# USB_3_0_eMMC.net
KiCad netlist of a schematic drawn in EAGLE
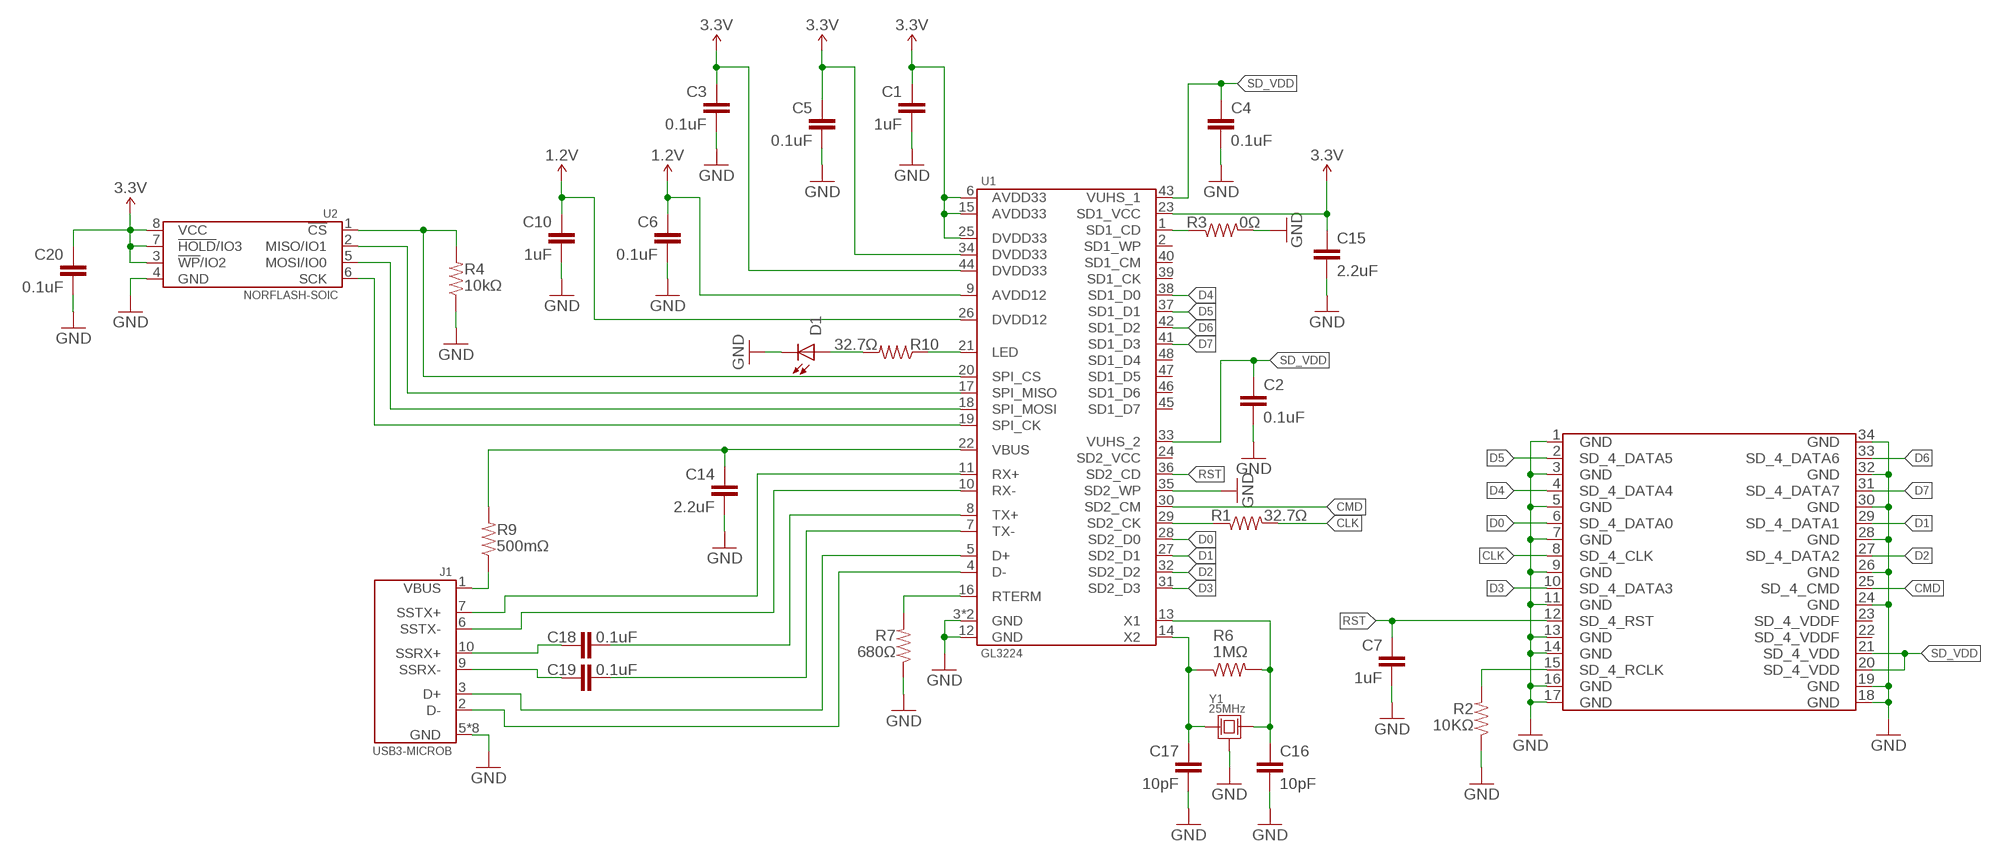
[diagram p0: schematic, sheet 1]

(export (version "E")
  (design (tool "Eeschema 10.0.6"))
  (components
    (comp (ref "C1")
      (value "1uF")
      (footprint "eagle-import:0402-CAP")
      (libsource (lib "eagle-import") (part "CAP-0402"))
    )
    (comp (ref "C2")
      (value "0.1uF")
      (footprint "eagle-import:0402-CAP")
      (libsource (lib "eagle-import") (part "CAP-0402"))
    )
    (comp (ref "C3")
      (value "0.1uF")
      (footprint "eagle-import:0402-CAP")
      (libsource (lib "eagle-import") (part "CAP-0402"))
    )
    (comp (ref "C4")
      (value "0.1uF")
      (footprint "eagle-import:0402-CAP")
      (libsource (lib "eagle-import") (part "CAP-0402"))
    )
    (comp (ref "C5")
      (value "0.1uF")
      (footprint "eagle-import:0402-CAP")
      (libsource (lib "eagle-import") (part "CAP-0402"))
    )
    (comp (ref "C6")
      (value "0.1uF")
      (footprint "eagle-import:0402-CAP")
      (libsource (lib "eagle-import") (part "CAP-0402"))
    )
    (comp (ref "C7")
      (value "1uF")
      (footprint "eagle-import:0402-CAP")
      (libsource (lib "eagle-import") (part "CAP-0402"))
    )
    (comp (ref "C10")
      (value "1uF")
      (footprint "eagle-import:0402-CAP")
      (libsource (lib "eagle-import") (part "CAP-0402"))
    )
    (comp (ref "C14")
      (value "2.2uF")
      (footprint "eagle-import:0402-CAP")
      (libsource (lib "eagle-import") (part "CAP-0402"))
    )
    (comp (ref "C15")
      (value "2.2uF")
      (footprint "eagle-import:0402-CAP")
      (libsource (lib "eagle-import") (part "CAP-0402"))
    )
    (comp (ref "C16")
      (value "10pF")
      (footprint "eagle-import:0402-CAP")
      (libsource (lib "eagle-import") (part "CAP-0402"))
    )
    (comp (ref "C17")
      (value "10pF")
      (footprint "eagle-import:0402-CAP")
      (libsource (lib "eagle-import") (part "CAP-0402"))
    )
    (comp (ref "C18")
      (value "0.1uF")
      (footprint "eagle-import:0402-CAP")
      (libsource (lib "eagle-import") (part "CAP-0402"))
    )
    (comp (ref "C19")
      (value "0.1uF")
      (footprint "eagle-import:0402-CAP")
      (libsource (lib "eagle-import") (part "CAP-0402"))
    )
    (comp (ref "C20")
      (value "0.1uF")
      (footprint "eagle-import:0402-CAP")
      (libsource (lib "eagle-import") (part "CAP-0402"))
    )
    (comp (ref "D1")
      (value "LED-0603")
      (footprint "eagle-import:0603-LED")
      (libsource (lib "eagle-import") (part "LED-0603"))
    )
    (comp (ref "J1")
      (value "USB3-MICROB")
      (footprint "eagle-import:USB-MICROB-3.1")
      (libsource (lib "eagle-import") (part "USB3-MICROB"))
    )
    (comp (ref "R1")
      (value "32.7Ω")
      (footprint "eagle-import:0402-RES")
      (libsource (lib "eagle-import") (part "RESISTOR-0402"))
    )
    (comp (ref "R2")
      (value "10KΩ")
      (footprint "eagle-import:0402-RES")
      (libsource (lib "eagle-import") (part "RESISTOR-0402"))
    )
    (comp (ref "R3")
      (value "0Ω")
      (footprint "eagle-import:0402-RES")
      (libsource (lib "eagle-import") (part "RESISTOR-0402"))
    )
    (comp (ref "R4")
      (value "10kΩ")
      (footprint "eagle-import:0402-RES")
      (libsource (lib "eagle-import") (part "RESISTOR-0402"))
    )
    (comp (ref "R6")
      (value "1MΩ")
      (footprint "eagle-import:0402-RES")
      (libsource (lib "eagle-import") (part "RESISTOR-0402"))
    )
    (comp (ref "R7")
      (value "680Ω")
      (footprint "eagle-import:0402-RES")
      (libsource (lib "eagle-import") (part "RESISTOR-0402"))
    )
    (comp (ref "R9")
      (value "500mΩ")
      (footprint "eagle-import:0805-RES")
      (libsource (lib "eagle-import") (part "RESISTOR-0805"))
    )
    (comp (ref "R10")
      (value "32.7Ω")
      (footprint "eagle-import:0402-RES")
      (libsource (lib "eagle-import") (part "RESISTOR-0402"))
    )
    (comp (ref "U1")
      (value "GL3224")
      (footprint "eagle-import:QFN48")
      (libsource (lib "eagle-import") (part "GL3224"))
    )
    (comp (ref "U2")
      (value "NORFLASH-SOIC")
      (footprint "eagle-import:SOIC-8")
      (libsource (lib "eagle-import") (part "NORFLASH-SOIC"))
    )
    (comp (ref "Y1")
      (value "25MHz")
      (footprint "eagle-import:FA-238")
      (libsource (lib "eagle-import") (part "CRYSTAL-3.2X2.5"))
    )
  )
  (nets
    (net (code "1") (name "1.2V") (class "Default")
      (node (ref "C10") (pin "1") (pinfunction "1_1") (pintype "passive"))
      (node (ref "C6") (pin "1") (pinfunction "1_1") (pintype "passive"))
      (node (ref "U1") (pin "26") (pinfunction "DVDD12_26") (pintype "bidirectional"))
      (node (ref "U1") (pin "9") (pinfunction "AVDD12_9") (pintype "bidirectional"))
    )
    (net (code "2") (name "3.3V") (class "Default")
      (node (ref "C1") (pin "1") (pinfunction "1_1") (pintype "passive"))
      (node (ref "C15") (pin "1") (pinfunction "1_1") (pintype "passive"))
      (node (ref "C20") (pin "1") (pinfunction "1_1") (pintype "passive"))
      (node (ref "C3") (pin "1") (pinfunction "1_1") (pintype "passive"))
      (node (ref "C5") (pin "1") (pinfunction "1_1") (pintype "passive"))
      (node (ref "U1") (pin "15") (pinfunction "AVDD33_15") (pintype "bidirectional"))
      (node (ref "U1") (pin "23") (pinfunction "SD1_VCC_23") (pintype "bidirectional"))
      (node (ref "U1") (pin "25") (pinfunction "DVDD33_25") (pintype "bidirectional"))
      (node (ref "U1") (pin "34") (pinfunction "DVDD33_34") (pintype "bidirectional"))
      (node (ref "U1") (pin "44") (pinfunction "DVDD33_44") (pintype "bidirectional"))
      (node (ref "U1") (pin "6") (pinfunction "AVDD33_6") (pintype "bidirectional"))
      (node (ref "U2") (pin "3") (pinfunction "~{WP}/IO2_3") (pintype "bidirectional"))
      (node (ref "U2") (pin "7") (pinfunction "~{HOLD}/IO3_7") (pintype "bidirectional"))
      (node (ref "U2") (pin "8") (pinfunction "VCC_8") (pintype "bidirectional"))
    )
    (net (code "3") (name "CLK") (class "Default")
      (node (ref "R1") (pin "2") (pinfunction "2_2") (pintype "passive"))
    )
    (net (code "4") (name "CMD") (class "Default")
      (node (ref "U1") (pin "30") (pinfunction "SD2_CM_30") (pintype "bidirectional"))
    )
    (net (code "5") (name "D0") (class "Default")
      (node (ref "U1") (pin "28") (pinfunction "SD2_D0_28") (pintype "bidirectional"))
    )
    (net (code "6") (name "D1") (class "Default")
      (node (ref "U1") (pin "27") (pinfunction "SD2_D1_27") (pintype "bidirectional"))
    )
    (net (code "7") (name "D2") (class "Default")
      (node (ref "U1") (pin "32") (pinfunction "SD2_D2_32") (pintype "bidirectional"))
    )
    (net (code "8") (name "D3") (class "Default")
      (node (ref "U1") (pin "31") (pinfunction "SD2_D3_31") (pintype "bidirectional"))
    )
    (net (code "9") (name "D4") (class "Default")
      (node (ref "U1") (pin "38") (pinfunction "SD1_D0_38") (pintype "bidirectional"))
    )
    (net (code "10") (name "D5") (class "Default")
      (node (ref "U1") (pin "37") (pinfunction "SD1_D1_37") (pintype "bidirectional"))
    )
    (net (code "11") (name "D6") (class "Default")
      (node (ref "U1") (pin "42") (pinfunction "SD1_D2_42") (pintype "bidirectional"))
    )
    (net (code "12") (name "D7") (class "Default")
      (node (ref "U1") (pin "41") (pinfunction "SD1_D3_41") (pintype "bidirectional"))
    )
    (net (code "13") (name "GND") (class "Default")
      (node (ref "C1") (pin "2") (pinfunction "2_2") (pintype "passive"))
      (node (ref "C10") (pin "2") (pinfunction "2_2") (pintype "passive"))
      (node (ref "C14") (pin "2") (pinfunction "2_2") (pintype "passive"))
      (node (ref "C15") (pin "2") (pinfunction "2_2") (pintype "passive"))
      (node (ref "C16") (pin "2") (pinfunction "2_2") (pintype "passive"))
      (node (ref "C17") (pin "2") (pinfunction "2_2") (pintype "passive"))
      (node (ref "C2") (pin "2") (pinfunction "2_2") (pintype "passive"))
      (node (ref "C20") (pin "2") (pinfunction "2_2") (pintype "passive"))
      (node (ref "C3") (pin "2") (pinfunction "2_2") (pintype "passive"))
      (node (ref "C4") (pin "2") (pinfunction "2_2") (pintype "passive"))
      (node (ref "C5") (pin "2") (pinfunction "2_2") (pintype "passive"))
      (node (ref "C6") (pin "2") (pinfunction "2_2") (pintype "passive"))
      (node (ref "C7") (pin "2") (pinfunction "2_2") (pintype "passive"))
      (node (ref "D1") (pin "C") (pinfunction "C_C") (pintype "passive"))
      (node (ref "J1") (pin "5") (pinfunction "GND_5") (pintype "bidirectional"))
      (node (ref "J1") (pin "8") (pinfunction "GND_8") (pintype "bidirectional"))
      (node (ref "J1") (pin "P$1") (pinfunction "GND_P$1") (pintype "bidirectional"))
      (node (ref "J1") (pin "P$2") (pinfunction "GND_P$2") (pintype "bidirectional"))
      (node (ref "J1") (pin "P$3") (pinfunction "GND_P$3") (pintype "bidirectional"))
      (node (ref "J1") (pin "P$4") (pinfunction "GND_P$4") (pintype "bidirectional"))
      (node (ref "J1") (pin "P$5") (pinfunction "GND_P$5") (pintype "bidirectional"))
      (node (ref "J1") (pin "P$6") (pinfunction "GND_P$6") (pintype "bidirectional"))
      (node (ref "R2") (pin "1") (pinfunction "1_1") (pintype "passive"))
      (node (ref "R3") (pin "2") (pinfunction "2_2") (pintype "passive"))
      (node (ref "R4") (pin "1") (pinfunction "1_1") (pintype "passive"))
      (node (ref "R7") (pin "1") (pinfunction "1_1") (pintype "passive"))
      (node (ref "U1") (pin "12") (pinfunction "GND_12") (pintype "bidirectional"))
      (node (ref "U1") (pin "3") (pinfunction "GND_3") (pintype "bidirectional"))
      (node (ref "U1") (pin "35") (pinfunction "SD2_WP_35") (pintype "bidirectional"))
      (node (ref "U1") (pin "PAD") (pinfunction "GND_PAD") (pintype "bidirectional"))
      (node (ref "U2") (pin "4") (pinfunction "GND_4") (pintype "bidirectional"))
      (node (ref "Y1") (pin "2") (pinfunction "GND_2") (pintype "bidirectional"))
      (node (ref "Y1") (pin "4") (pinfunction "GND_4") (pintype "bidirectional"))
    )
    (net (code "14") (name "Net-(D1-PadA)") (class "Default")
      (node (ref "D1") (pin "A") (pinfunction "A_A") (pintype "passive"))
      (node (ref "R10") (pin "2") (pinfunction "2_2") (pintype "passive"))
    )
    (net (code "15") (name "Net-(J1-D+)") (class "Default")
      (node (ref "J1") (pin "3") (pinfunction "D+_3") (pintype "bidirectional"))
      (node (ref "U1") (pin "5") (pinfunction "D+_5") (pintype "bidirectional"))
    )
    (net (code "16") (name "Net-(J1-D-)") (class "Default")
      (node (ref "J1") (pin "2") (pinfunction "D-_2") (pintype "bidirectional"))
      (node (ref "U1") (pin "4") (pinfunction "D-_4") (pintype "bidirectional"))
    )
    (net (code "17") (name "Net-(J1-SSRX+)") (class "Default")
      (node (ref "C18") (pin "1") (pinfunction "1_1") (pintype "passive"))
      (node (ref "J1") (pin "10") (pinfunction "SSRX+_10") (pintype "bidirectional"))
    )
    (net (code "18") (name "Net-(J1-SSRX-)") (class "Default")
      (node (ref "C19") (pin "1") (pinfunction "1_1") (pintype "passive"))
      (node (ref "J1") (pin "9") (pinfunction "SSRX-_9") (pintype "bidirectional"))
    )
    (net (code "19") (name "Net-(J1-SSTX+)") (class "Default")
      (node (ref "J1") (pin "7") (pinfunction "SSTX+_7") (pintype "bidirectional"))
      (node (ref "U1") (pin "11") (pinfunction "RX+_11") (pintype "bidirectional"))
    )
    (net (code "20") (name "Net-(J1-SSTX-)") (class "Default")
      (node (ref "J1") (pin "6") (pinfunction "SSTX-_6") (pintype "bidirectional"))
      (node (ref "U1") (pin "10") (pinfunction "RX-_10") (pintype "bidirectional"))
    )
    (net (code "21") (name "Net-(J1-VBUS)") (class "Default")
      (node (ref "J1") (pin "1") (pinfunction "VBUS_1") (pintype "bidirectional"))
      (node (ref "R9") (pin "1") (pinfunction "1_1") (pintype "passive"))
    )
    (net (code "22") (name "Net-(U1-LED)") (class "Default")
      (node (ref "R10") (pin "1") (pinfunction "1_1") (pintype "passive"))
      (node (ref "U1") (pin "21") (pinfunction "LED_21") (pintype "bidirectional"))
    )
    (net (code "23") (name "Net-(U1-RTERM)") (class "Default")
      (node (ref "R7") (pin "2") (pinfunction "2_2") (pintype "passive"))
      (node (ref "U1") (pin "16") (pinfunction "RTERM_16") (pintype "bidirectional"))
    )
    (net (code "24") (name "Net-(U1-SD1_CD)") (class "Default")
      (node (ref "R3") (pin "1") (pinfunction "1_1") (pintype "passive"))
      (node (ref "U1") (pin "1") (pinfunction "SD1_CD_1") (pintype "bidirectional"))
    )
    (net (code "25") (name "Net-(U1-SD2_CK)") (class "Default")
      (node (ref "R1") (pin "1") (pinfunction "1_1") (pintype "passive"))
      (node (ref "U1") (pin "29") (pinfunction "SD2_CK_29") (pintype "bidirectional"))
    )
    (net (code "26") (name "Net-(U1-SPI_CK)") (class "Default")
      (node (ref "U1") (pin "19") (pinfunction "SPI_CK_19") (pintype "bidirectional"))
      (node (ref "U2") (pin "6") (pinfunction "SCK_6") (pintype "bidirectional"))
    )
    (net (code "27") (name "Net-(U1-SPI_CS)") (class "Default")
      (node (ref "R4") (pin "2") (pinfunction "2_2") (pintype "passive"))
      (node (ref "U1") (pin "20") (pinfunction "SPI_CS_20") (pintype "bidirectional"))
      (node (ref "U2") (pin "1") (pinfunction "~{CS}_1") (pintype "bidirectional"))
    )
    (net (code "28") (name "Net-(U1-SPI_MISO)") (class "Default")
      (node (ref "U1") (pin "17") (pinfunction "SPI_MISO_17") (pintype "bidirectional"))
      (node (ref "U2") (pin "2") (pinfunction "MISO/IO1_2") (pintype "bidirectional"))
    )
    (net (code "29") (name "Net-(U1-SPI_MOSI)") (class "Default")
      (node (ref "U1") (pin "18") (pinfunction "SPI_MOSI_18") (pintype "bidirectional"))
      (node (ref "U2") (pin "5") (pinfunction "MOSI/IO0_5") (pintype "bidirectional"))
    )
    (net (code "30") (name "Net-(U1-TX+)") (class "Default")
      (node (ref "C18") (pin "2") (pinfunction "2_2") (pintype "passive"))
      (node (ref "U1") (pin "8") (pinfunction "TX+_8") (pintype "bidirectional"))
    )
    (net (code "31") (name "Net-(U1-TX-)") (class "Default")
      (node (ref "C19") (pin "2") (pinfunction "2_2") (pintype "passive"))
      (node (ref "U1") (pin "7") (pinfunction "TX-_7") (pintype "bidirectional"))
    )
    (net (code "32") (name "Net-(U1-VBUS)") (class "Default")
      (node (ref "C14") (pin "1") (pinfunction "1_1") (pintype "passive"))
      (node (ref "R9") (pin "2") (pinfunction "2_2") (pintype "passive"))
      (node (ref "U1") (pin "22") (pinfunction "VBUS_22") (pintype "bidirectional"))
    )
    (net (code "33") (name "Net-(U1-X1)") (class "Default")
      (node (ref "C16") (pin "1") (pinfunction "1_1") (pintype "passive"))
      (node (ref "R6") (pin "2") (pinfunction "2_2") (pintype "passive"))
      (node (ref "U1") (pin "13") (pinfunction "X1_13") (pintype "bidirectional"))
      (node (ref "Y1") (pin "3") (pinfunction "2_3") (pintype "bidirectional"))
    )
    (net (code "34") (name "Net-(U1-X2)") (class "Default")
      (node (ref "C17") (pin "1") (pinfunction "1_1") (pintype "passive"))
      (node (ref "R6") (pin "1") (pinfunction "1_1") (pintype "passive"))
      (node (ref "U1") (pin "14") (pinfunction "X2_14") (pintype "bidirectional"))
      (node (ref "Y1") (pin "1") (pinfunction "1_1") (pintype "bidirectional"))
    )
    (net (code "35") (name "RST") (class "Default")
      (node (ref "C7") (pin "1") (pinfunction "1_1") (pintype "passive"))
      (node (ref "U1") (pin "36") (pinfunction "SD2_CD_36") (pintype "bidirectional"))
    )
    (net (code "36") (name "SD_VDD") (class "Default")
      (node (ref "C2") (pin "1") (pinfunction "1_1") (pintype "passive"))
      (node (ref "C4") (pin "1") (pinfunction "1_1") (pintype "passive"))
      (node (ref "U1") (pin "33") (pinfunction "VUHS_2_33") (pintype "bidirectional"))
      (node (ref "U1") (pin "43") (pinfunction "VUHS_1_43") (pintype "bidirectional"))
    )
    (net (code "37") (name "unconnected-(R2-Pad2)") (class "Default")
      (node (ref "R2") (pin "2") (pinfunction "2_2") (pintype "passive"))
    )
    (net (code "38") (name "unconnected-(U1-SD1_CK-Pad39)") (class "Default")
      (node (ref "U1") (pin "39") (pinfunction "SD1_CK_39") (pintype "bidirectional"))
    )
    (net (code "39") (name "unconnected-(U1-SD1_CM-Pad40)") (class "Default")
      (node (ref "U1") (pin "40") (pinfunction "SD1_CM_40") (pintype "bidirectional"))
    )
    (net (code "40") (name "unconnected-(U1-SD1_D4-Pad48)") (class "Default")
      (node (ref "U1") (pin "48") (pinfunction "SD1_D4_48") (pintype "bidirectional"))
    )
    (net (code "41") (name "unconnected-(U1-SD1_D5-Pad47)") (class "Default")
      (node (ref "U1") (pin "47") (pinfunction "SD1_D5_47") (pintype "bidirectional"))
    )
    (net (code "42") (name "unconnected-(U1-SD1_D6-Pad46)") (class "Default")
      (node (ref "U1") (pin "46") (pinfunction "SD1_D6_46") (pintype "bidirectional"))
    )
    (net (code "43") (name "unconnected-(U1-SD1_D7-Pad45)") (class "Default")
      (node (ref "U1") (pin "45") (pinfunction "SD1_D7_45") (pintype "bidirectional"))
    )
    (net (code "44") (name "unconnected-(U1-SD1_WP-Pad2)") (class "Default")
      (node (ref "U1") (pin "2") (pinfunction "SD1_WP_2") (pintype "bidirectional"))
    )
    (net (code "45") (name "unconnected-(U1-SD2_VCC-Pad24)") (class "Default")
      (node (ref "U1") (pin "24") (pinfunction "SD2_VCC_24") (pintype "bidirectional"))
    )
  )
)
